# PWR_MGMT.net
KiCad netlist of a schematic drawn in Altium Designer
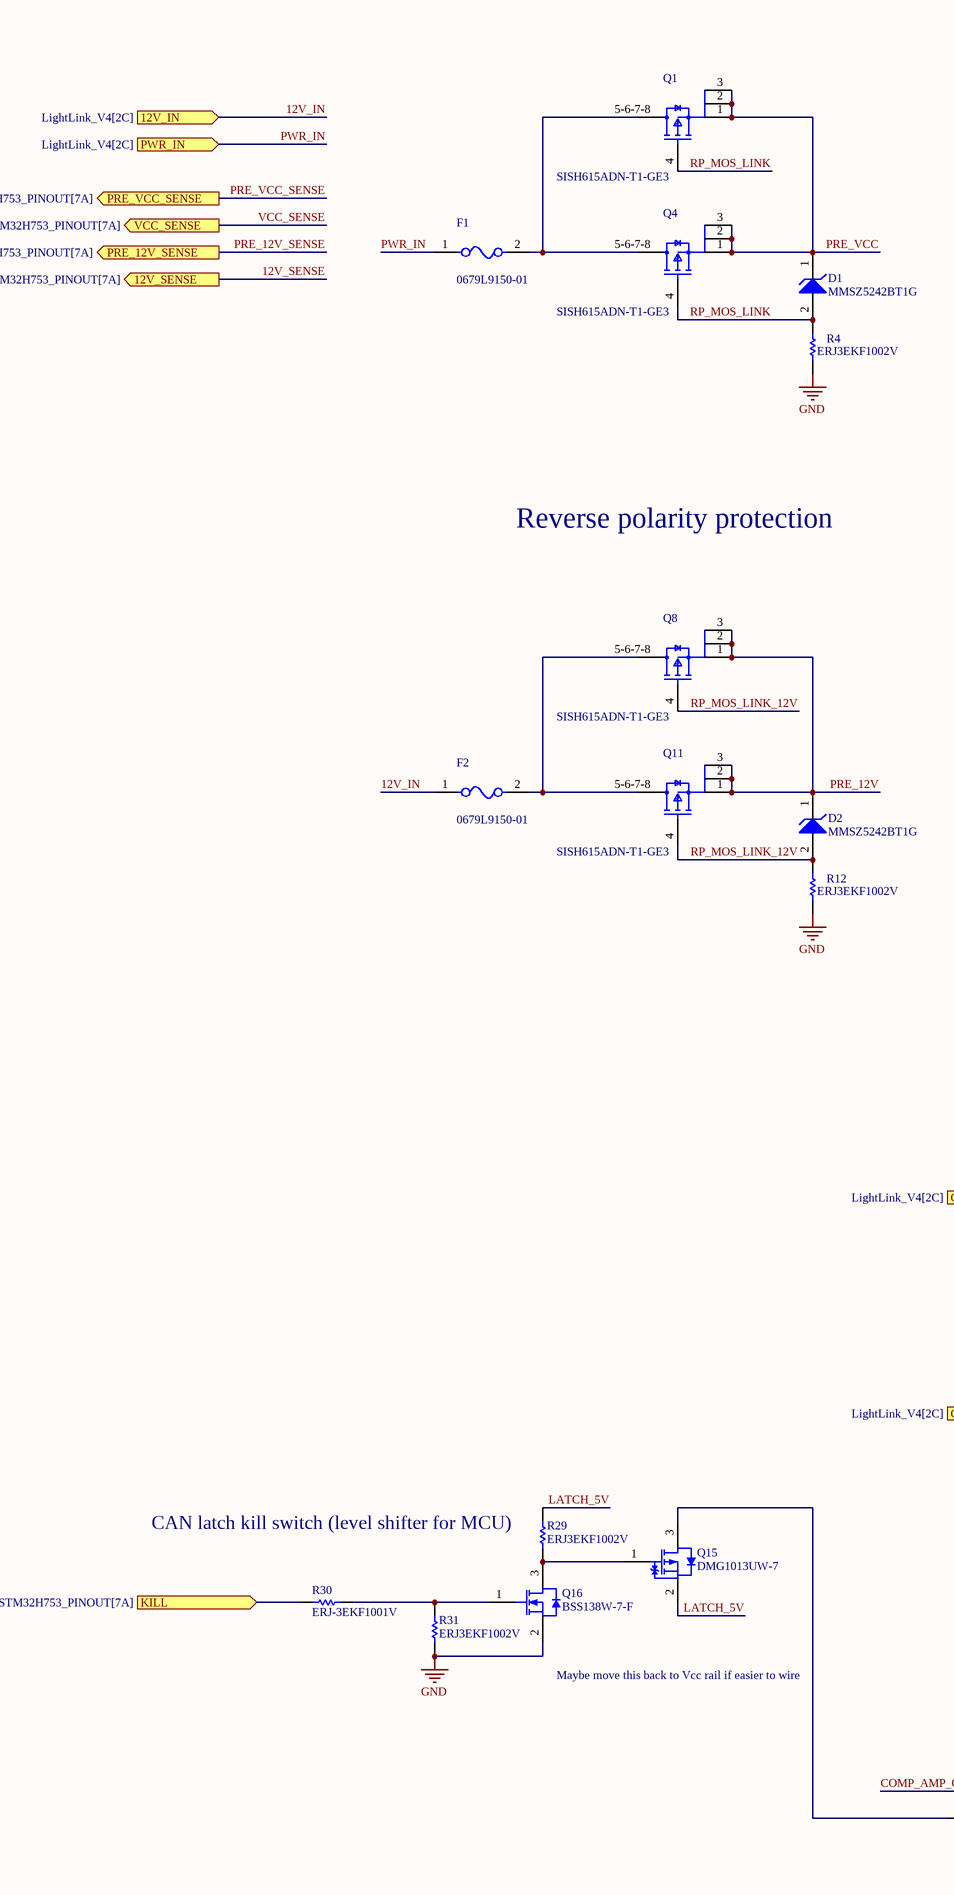
[diagram p0: PWR_MGMT.SchDoc, left]
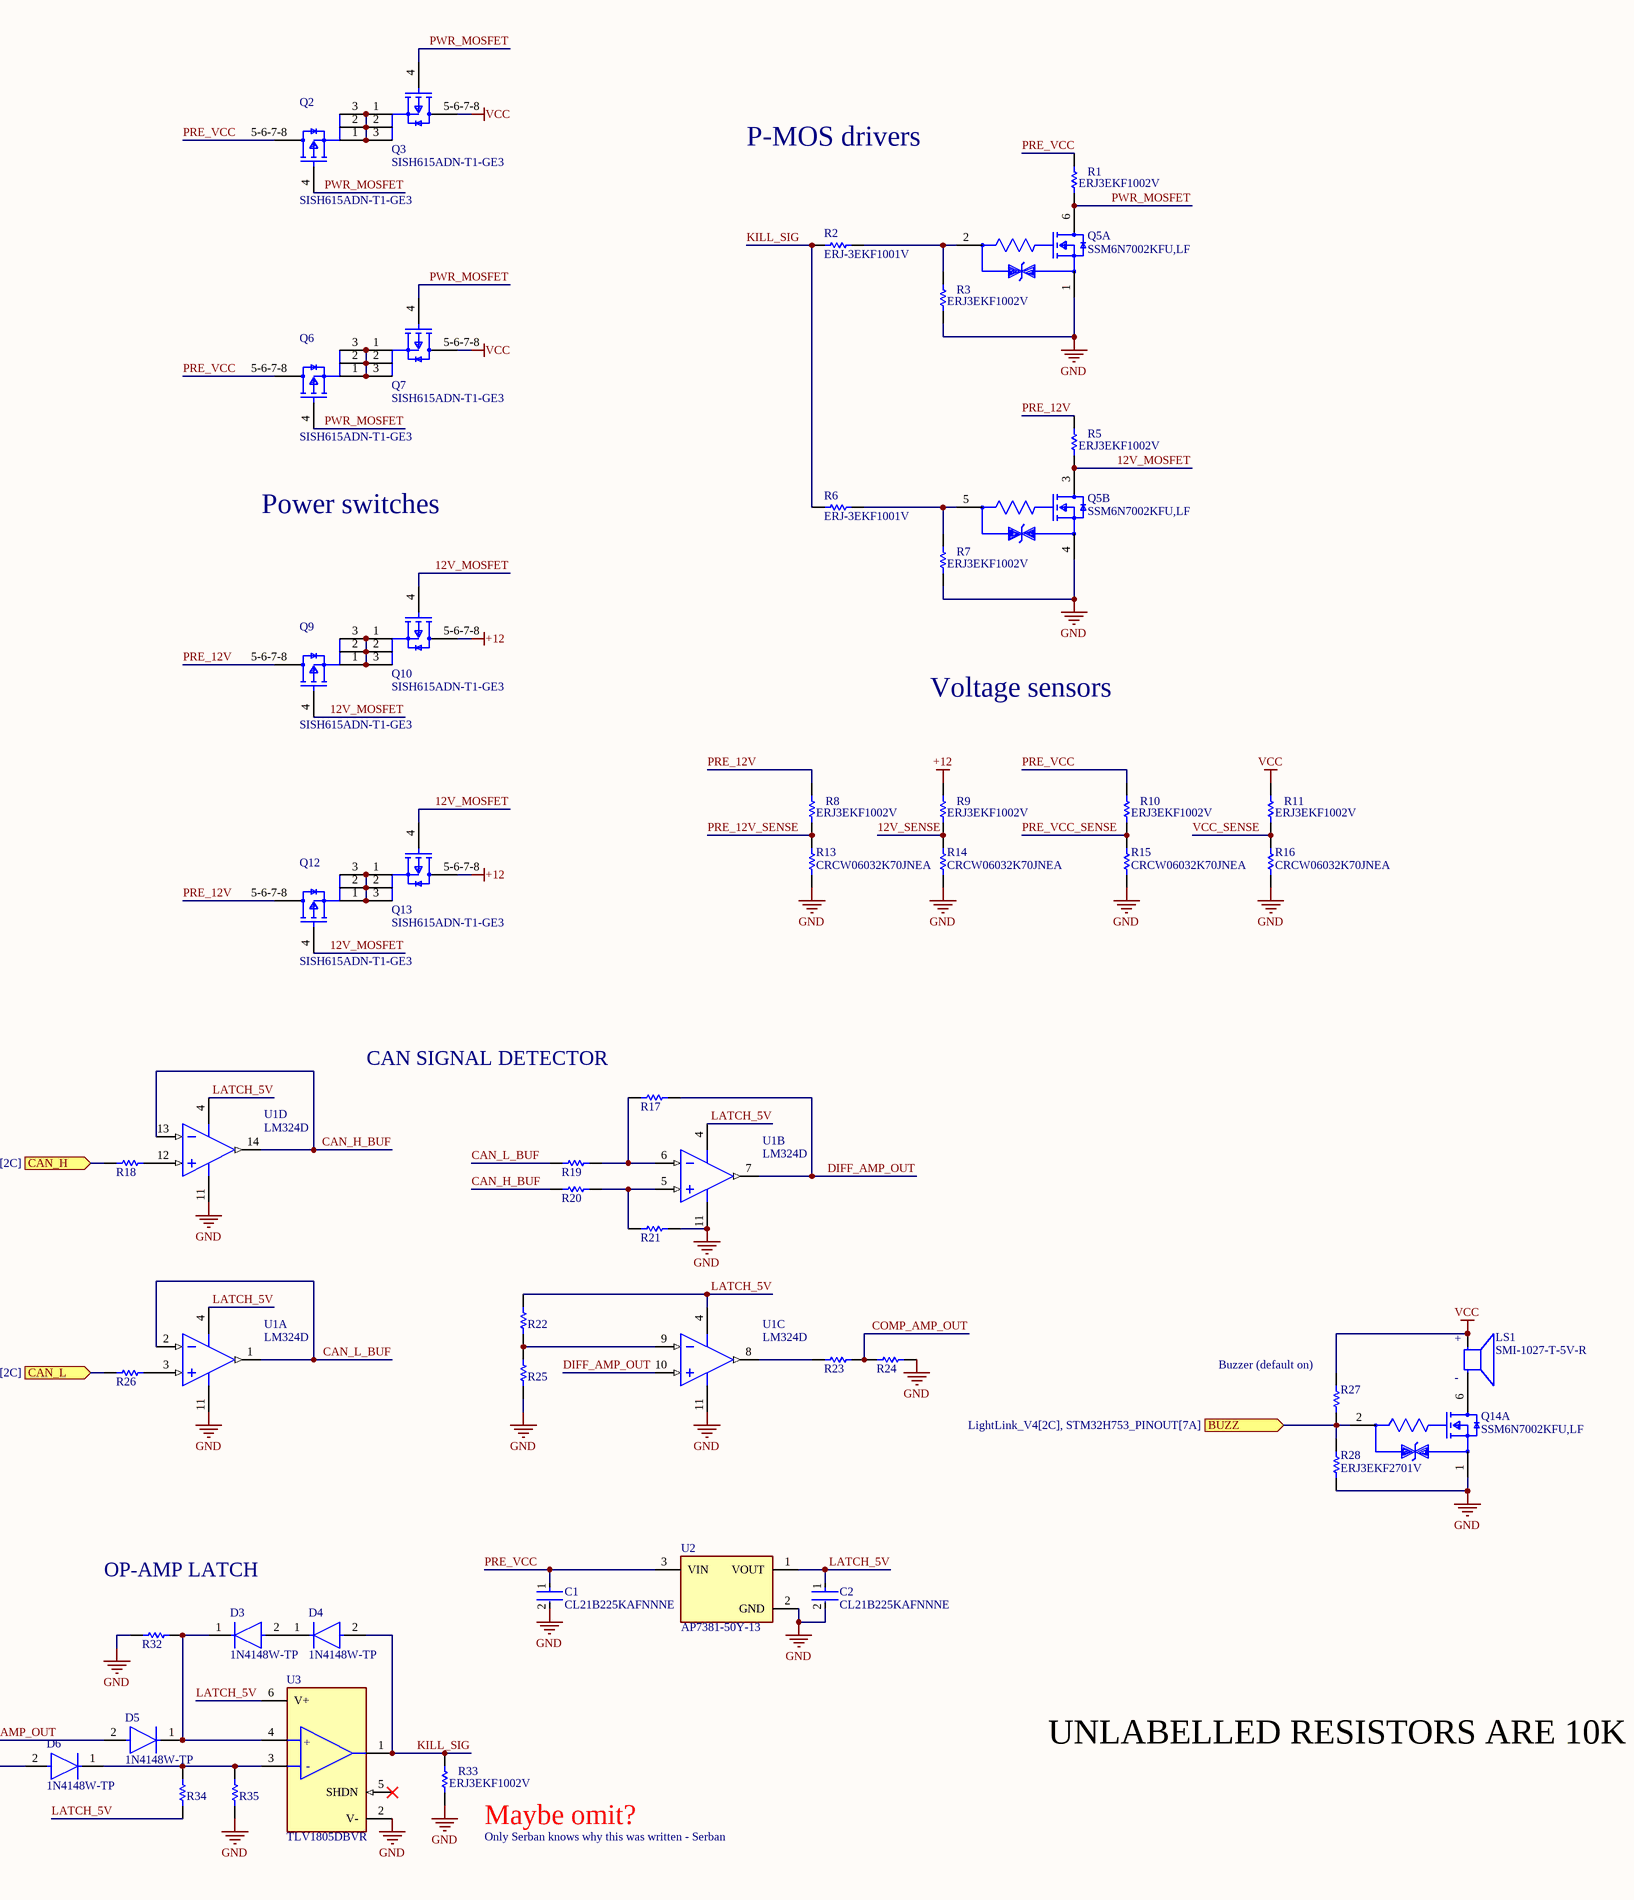
[diagram p1: PWR_MGMT.SchDoc, right]

(export (version "E")
  (design (tool "Eeschema 10.0.6"))
  (components
    (comp (ref "C1")
      (value "CL21B225KAFNNNE")
      (footprint "FP-0805-L_2_01_0_2-W_1_25-IPC_B")
      (fields (field (name "TOLERANCE") "10%") (field (name "VOLTAGE") "25V"))
      (libsource (lib "Altium Content Vault") (part "02cd4be3c70576c341d710602a673aa"))
    )
    (comp (ref "C2")
      (value "CL21B225KAFNNNE")
      (footprint "FP-0805-L_2_01_0_2-W_1_25-IPC_B")
      (fields (field (name "TOLERANCE") "10%") (field (name "VOLTAGE") "25V"))
      (libsource (lib "Altium Content Vault") (part "02cd4be3c70576c341d710602a673aa"))
    )
    (comp (ref "D1")
      (value "MMSZ5242BT1G")
      (footprint "ONSC-SOD-123-2-425-04_V")
      (description "Zener Voltage Regulator, 500 mW, 2-Pin SOD-123, Pb-Free, Tape and Reel")
      (fields (field (name "MANUFACTURER") "On Semiconductor"))
      (libsource (lib "Altium Content Vault") (part "ONSC-K1A2-2"))
    )
    (comp (ref "D2")
      (value "MMSZ5242BT1G")
      (footprint "ONSC-SOD-123-2-425-04_V")
      (description "Zener Voltage Regulator, 500 mW, 2-Pin SOD-123, Pb-Free, Tape and Reel")
      (fields (field (name "MANUFACTURER") "On Semiconductor"))
      (libsource (lib "Altium Content Vault") (part "ONSC-K1A2-2"))
    )
    (comp (ref "D3")
      (value "1N4148W-TP")
      (footprint "FP-SOD-123-IPC_A")
      (description "DIODE GEN PURP 100V 150MA SOD123")
      (libsource (lib "Altium Content Vault") (part "d7152d700b627762746794eb795d46e"))
    )
    (comp (ref "D4")
      (value "1N4148W-TP")
      (footprint "FP-SOD-123-IPC_A")
      (description "DIODE GEN PURP 100V 150MA SOD123")
      (libsource (lib "Altium Content Vault") (part "d7152d700b627762746794eb795d46e"))
    )
    (comp (ref "D5")
      (value "1N4148W-TP")
      (footprint "FP-SOD-123-IPC_A")
      (description "DIODE GEN PURP 100V 150MA SOD123")
      (libsource (lib "Altium Content Vault") (part "d7152d700b627762746794eb795d46e"))
    )
    (comp (ref "D6")
      (value "1N4148W-TP")
      (footprint "FP-SOD-123-IPC_A")
      (description "DIODE GEN PURP 100V 150MA SOD123")
      (libsource (lib "Altium Content Vault") (part "d7152d700b627762746794eb795d46e"))
    )
    (comp (ref "F1")
      (value "0679L9150-01")
      (footprint "FP-0679L-MFG")
      (description "FUSE BRD MNT 15A 125VAC/VDC")
      (fields
        (field (name "OCTOPART") "https://octopart.com/0679l9150-01-bel+fuse-70850665")
        (field (name "MANUFACTURER") "Bel Fuse")
      )
      (libsource (lib "Altium Content Vault") (part "5bcf9b9f640e542cf0359d10258e979"))
    )
    (comp (ref "F2")
      (value "0679L9150-01")
      (footprint "FP-0679L-MFG")
      (description "FUSE BRD MNT 15A 125VAC/VDC")
      (fields
        (field (name "OCTOPART") "https://octopart.com/0679l9150-01-bel+fuse-70850665")
        (field (name "MANUFACTURER") "Bel Fuse")
      )
      (libsource (lib "Altium Content Vault") (part "5bcf9b9f640e542cf0359d10258e979"))
    )
    (comp (ref "LS1")
      (value "SMI-1027-T-5V-R")
      (footprint "SMI-1027-T-5V-R-Footprint-1")
      (description "Audio Ind Magnt 5V 9.6X9.6MM SMD")
      (libsource (lib "uORocketry Hardware") (part "SMI-1027-T-5V-R"))
    )
    (comp (ref "Q1")
      (value "SISH615ADN-T1-GE3")
      (footprint "SISH615ADN-T1-GE3-Footprint-1")
      (description "Trans MOSFET P-CH 20V 22.1A 8-Pin PowerPAK 1212 EP T/R")
      (libsource (lib "uORocketry Hardware") (part "SISH615ADN-T1-GE3-Symbol-1"))
    )
    (comp (ref "Q2")
      (value "SISH615ADN-T1-GE3")
      (footprint "SISH615ADN-T1-GE3-Footprint-1")
      (description "Trans MOSFET P-CH 20V 22.1A 8-Pin PowerPAK 1212 EP T/R")
      (libsource (lib "uORocketry Hardware") (part "SISH615ADN-T1-GE3-Symbol-1"))
    )
    (comp (ref "Q3")
      (value "SISH615ADN-T1-GE3")
      (footprint "SISH615ADN-T1-GE3-Footprint-1")
      (description "Trans MOSFET P-CH 20V 22.1A 8-Pin PowerPAK 1212 EP T/R")
      (libsource (lib "uORocketry Hardware") (part "SISH615ADN-T1-GE3-Symbol-1"))
    )
    (comp (ref "Q4")
      (value "SISH615ADN-T1-GE3")
      (footprint "SISH615ADN-T1-GE3-Footprint-1")
      (description "Trans MOSFET P-CH 20V 22.1A 8-Pin PowerPAK 1212 EP T/R")
      (libsource (lib "uORocketry Hardware") (part "SISH615ADN-T1-GE3-Symbol-1"))
    )
    (comp (ref "Q5")
      (value "SSM6N7002KFU,LF")
      (footprint "FP-SSOP6-P-0_65A-MFG")
      (description "MOSFET 2N-CH 60V 0.3A")
      (libsource (lib "Altium Content Vault") (part "088aa6ac103fdeebe0d1c52ece6b7b9"))
    )
    (comp (ref "Q6")
      (value "SISH615ADN-T1-GE3")
      (footprint "SISH615ADN-T1-GE3-Footprint-1")
      (description "Trans MOSFET P-CH 20V 22.1A 8-Pin PowerPAK 1212 EP T/R")
      (libsource (lib "uORocketry Hardware") (part "SISH615ADN-T1-GE3-Symbol-1"))
    )
    (comp (ref "Q7")
      (value "SISH615ADN-T1-GE3")
      (footprint "SISH615ADN-T1-GE3-Footprint-1")
      (description "Trans MOSFET P-CH 20V 22.1A 8-Pin PowerPAK 1212 EP T/R")
      (libsource (lib "uORocketry Hardware") (part "SISH615ADN-T1-GE3-Symbol-1"))
    )
    (comp (ref "Q8")
      (value "SISH615ADN-T1-GE3")
      (footprint "SISH615ADN-T1-GE3-Footprint-1")
      (description "Trans MOSFET P-CH 20V 22.1A 8-Pin PowerPAK 1212 EP T/R")
      (libsource (lib "uORocketry Hardware") (part "SISH615ADN-T1-GE3-Symbol-1"))
    )
    (comp (ref "Q9")
      (value "SISH615ADN-T1-GE3")
      (footprint "SISH615ADN-T1-GE3-Footprint-1")
      (description "Trans MOSFET P-CH 20V 22.1A 8-Pin PowerPAK 1212 EP T/R")
      (libsource (lib "uORocketry Hardware") (part "SISH615ADN-T1-GE3-Symbol-1"))
    )
    (comp (ref "Q10")
      (value "SISH615ADN-T1-GE3")
      (footprint "SISH615ADN-T1-GE3-Footprint-1")
      (description "Trans MOSFET P-CH 20V 22.1A 8-Pin PowerPAK 1212 EP T/R")
      (libsource (lib "uORocketry Hardware") (part "SISH615ADN-T1-GE3-Symbol-1"))
    )
    (comp (ref "Q11")
      (value "SISH615ADN-T1-GE3")
      (footprint "SISH615ADN-T1-GE3-Footprint-1")
      (description "Trans MOSFET P-CH 20V 22.1A 8-Pin PowerPAK 1212 EP T/R")
      (libsource (lib "uORocketry Hardware") (part "SISH615ADN-T1-GE3-Symbol-1"))
    )
    (comp (ref "Q12")
      (value "SISH615ADN-T1-GE3")
      (footprint "SISH615ADN-T1-GE3-Footprint-1")
      (description "Trans MOSFET P-CH 20V 22.1A 8-Pin PowerPAK 1212 EP T/R")
      (libsource (lib "uORocketry Hardware") (part "SISH615ADN-T1-GE3-Symbol-1"))
    )
    (comp (ref "Q13")
      (value "SISH615ADN-T1-GE3")
      (footprint "SISH615ADN-T1-GE3-Footprint-1")
      (description "Trans MOSFET P-CH 20V 22.1A 8-Pin PowerPAK 1212 EP T/R")
      (libsource (lib "uORocketry Hardware") (part "SISH615ADN-T1-GE3-Symbol-1"))
    )
    (comp (ref "Q14")
      (value "SSM6N7002KFU,LF")
      (footprint "FP-SSOP6-P-0_65A-MFG")
      (description "MOSFET 2N-CH 60V 0.3A")
      (libsource (lib "Altium Content Vault") (part "088aa6ac103fdeebe0d1c52ece6b7b9"))
    )
    (comp (ref "Q15")
      (value "DMG1013UW-7")
      (footprint "DIOD-SOT323-3_V")
      (fields (field (name "MANUFACTURER") "Diodes Inc"))
      (libsource (lib "Altium Content Vault") (part "PEMOS-GSD-3_C"))
    )
    (comp (ref "Q16")
      (value "BSS138W-7-F")
      (footprint "DIOD-SOT323-3_V")
      (fields (field (name "MANUFACTURER") "DiodesIncorporated"))
      (libsource (lib "Altium Content Vault") (part "NEMOS-GSD-3"))
    )
    (comp (ref "R1")
      (value "ERJ3EKF1002V")
      (footprint "RESC1609X55X30LL15T15")
      (description "Chip Resistor, 10 KOhm, +/- 1%, 0.1 W, -55 to 155 degC, 0603 (1608 Metric), RoHS, Tape and Reel")
      (fields (field (name "TOLERANCE") "1%") (field (name "MANUFACTURER") "Panasonic"))
      (libsource (lib "Altium Content Vault") (part "RES-2"))
    )
    (comp (ref "R2")
      (value "ERJ-3EKF1001V")
      (footprint "RESC1608X55X30LL15T15")
      (fields (field (name "MANUFACTURER") "Panasonic"))
      (libsource (lib "Altium Content Vault") (part "RES"))
    )
    (comp (ref "R3")
      (value "ERJ3EKF1002V")
      (footprint "RESC1609X55X30LL15T15")
      (description "Chip Resistor, 10 KOhm, +/- 1%, 0.1 W, -55 to 155 degC, 0603 (1608 Metric), RoHS, Tape and Reel")
      (fields (field (name "TOLERANCE") "1%") (field (name "MANUFACTURER") "Panasonic"))
      (libsource (lib "Altium Content Vault") (part "RES-2"))
    )
    (comp (ref "R4")
      (value "ERJ3EKF1002V")
      (footprint "RESC1609X55X30LL15T15")
      (description "Chip Resistor, 10 KOhm, +/- 1%, 0.1 W, -55 to 155 degC, 0603 (1608 Metric), RoHS, Tape and Reel")
      (fields (field (name "TOLERANCE") "1%") (field (name "MANUFACTURER") "Panasonic"))
      (libsource (lib "Altium Content Vault") (part "RES-2"))
    )
    (comp (ref "R5")
      (value "ERJ3EKF1002V")
      (footprint "RESC1609X55X30LL15T15")
      (description "Chip Resistor, 10 KOhm, +/- 1%, 0.1 W, -55 to 155 degC, 0603 (1608 Metric), RoHS, Tape and Reel")
      (fields (field (name "TOLERANCE") "1%") (field (name "MANUFACTURER") "Panasonic"))
      (libsource (lib "Altium Content Vault") (part "RES-2"))
    )
    (comp (ref "R6")
      (value "ERJ-3EKF1001V")
      (footprint "RESC1608X55X30LL15T15")
      (fields (field (name "MANUFACTURER") "Panasonic"))
      (libsource (lib "Altium Content Vault") (part "RES"))
    )
    (comp (ref "R7")
      (value "ERJ3EKF1002V")
      (footprint "RESC1609X55X30LL15T15")
      (description "Chip Resistor, 10 KOhm, +/- 1%, 0.1 W, -55 to 155 degC, 0603 (1608 Metric), RoHS, Tape and Reel")
      (fields (field (name "TOLERANCE") "1%") (field (name "MANUFACTURER") "Panasonic"))
      (libsource (lib "Altium Content Vault") (part "RES-2"))
    )
    (comp (ref "R8")
      (value "ERJ3EKF1002V")
      (footprint "RESC1609X55X30LL15T15")
      (description "Chip Resistor, 10 KOhm, +/- 1%, 0.1 W, -55 to 155 degC, 0603 (1608 Metric), RoHS, Tape and Reel")
      (fields (field (name "TOLERANCE") "1%") (field (name "MANUFACTURER") "Panasonic"))
      (libsource (lib "Altium Content Vault") (part "RES-2"))
    )
    (comp (ref "R9")
      (value "ERJ3EKF1002V")
      (footprint "RESC1609X55X30LL15T15")
      (description "Chip Resistor, 10 KOhm, +/- 1%, 0.1 W, -55 to 155 degC, 0603 (1608 Metric), RoHS, Tape and Reel")
      (fields (field (name "TOLERANCE") "1%") (field (name "MANUFACTURER") "Panasonic"))
      (libsource (lib "Altium Content Vault") (part "RES-2"))
    )
    (comp (ref "R10")
      (value "ERJ3EKF1002V")
      (footprint "RESC1609X55X30LL15T15")
      (description "Chip Resistor, 10 KOhm, +/- 1%, 0.1 W, -55 to 155 degC, 0603 (1608 Metric), RoHS, Tape and Reel")
      (fields (field (name "TOLERANCE") "1%") (field (name "MANUFACTURER") "Panasonic"))
      (libsource (lib "Altium Content Vault") (part "RES-2"))
    )
    (comp (ref "R11")
      (value "ERJ3EKF1002V")
      (footprint "RESC1609X55X30LL15T15")
      (description "Chip Resistor, 10 KOhm, +/- 1%, 0.1 W, -55 to 155 degC, 0603 (1608 Metric), RoHS, Tape and Reel")
      (fields (field (name "TOLERANCE") "1%") (field (name "MANUFACTURER") "Panasonic"))
      (libsource (lib "Altium Content Vault") (part "RES-2"))
    )
    (comp (ref "R12")
      (value "ERJ3EKF1002V")
      (footprint "RESC1609X55X30LL15T15")
      (description "Chip Resistor, 10 KOhm, +/- 1%, 0.1 W, -55 to 155 degC, 0603 (1608 Metric), RoHS, Tape and Reel")
      (fields (field (name "TOLERANCE") "1%") (field (name "MANUFACTURER") "Panasonic"))
      (libsource (lib "Altium Content Vault") (part "RES-2"))
    )
    (comp (ref "R13")
      (value "CRCW06032K70JNEA")
      (footprint "RESC1609X50X30ML10T20")
      (fields (field (name "MANUFACTURER") "Vishay Dale"))
      (libsource (lib "Altium Content Vault") (part "RES"))
    )
    (comp (ref "R14")
      (value "CRCW06032K70JNEA")
      (footprint "RESC1609X50X30ML10T20")
      (fields (field (name "MANUFACTURER") "Vishay Dale"))
      (libsource (lib "Altium Content Vault") (part "RES"))
    )
    (comp (ref "R15")
      (value "CRCW06032K70JNEA")
      (footprint "RESC1609X50X30ML10T20")
      (fields (field (name "MANUFACTURER") "Vishay Dale"))
      (libsource (lib "Altium Content Vault") (part "RES"))
    )
    (comp (ref "R16")
      (value "CRCW06032K70JNEA")
      (footprint "RESC1609X50X30ML10T20")
      (fields (field (name "MANUFACTURER") "Vishay Dale"))
      (libsource (lib "Altium Content Vault") (part "RES"))
    )
    (comp (ref "R17")
      (value "ERJ3EKF1002V")
      (footprint "RESC1609X55X30LL15T15")
      (description "Chip Resistor, 10 KOhm, +/- 1%, 0.1 W, -55 to 155 degC, 0603 (1608 Metric), RoHS, Tape and Reel")
      (fields (field (name "TOLERANCE") "1%") (field (name "MANUFACTURER") "Panasonic"))
      (libsource (lib "Altium Content Vault") (part "RES-2"))
    )
    (comp (ref "R18")
      (value "ERJ3EKF1002V")
      (footprint "RESC1609X55X30LL15T15")
      (description "Chip Resistor, 10 KOhm, +/- 1%, 0.1 W, -55 to 155 degC, 0603 (1608 Metric), RoHS, Tape and Reel")
      (fields (field (name "TOLERANCE") "1%") (field (name "MANUFACTURER") "Panasonic"))
      (libsource (lib "Altium Content Vault") (part "RES-2"))
    )
    (comp (ref "R19")
      (value "ERJ3EKF1002V")
      (footprint "RESC1609X55X30LL15T15")
      (description "Chip Resistor, 10 KOhm, +/- 1%, 0.1 W, -55 to 155 degC, 0603 (1608 Metric), RoHS, Tape and Reel")
      (fields (field (name "TOLERANCE") "1%") (field (name "MANUFACTURER") "Panasonic"))
      (libsource (lib "Altium Content Vault") (part "RES-2"))
    )
    (comp (ref "R20")
      (value "ERJ3EKF1002V")
      (footprint "RESC1609X55X30LL15T15")
      (description "Chip Resistor, 10 KOhm, +/- 1%, 0.1 W, -55 to 155 degC, 0603 (1608 Metric), RoHS, Tape and Reel")
      (fields (field (name "TOLERANCE") "1%") (field (name "MANUFACTURER") "Panasonic"))
      (libsource (lib "Altium Content Vault") (part "RES-2"))
    )
    (comp (ref "R21")
      (value "ERJ3EKF1002V")
      (footprint "RESC1609X55X30LL15T15")
      (description "Chip Resistor, 10 KOhm, +/- 1%, 0.1 W, -55 to 155 degC, 0603 (1608 Metric), RoHS, Tape and Reel")
      (fields (field (name "TOLERANCE") "1%") (field (name "MANUFACTURER") "Panasonic"))
      (libsource (lib "Altium Content Vault") (part "RES-2"))
    )
    (comp (ref "R22")
      (value "ERJ3EKF1002V")
      (footprint "RESC1609X55X30LL15T15")
      (description "Chip Resistor, 10 KOhm, +/- 1%, 0.1 W, -55 to 155 degC, 0603 (1608 Metric), RoHS, Tape and Reel")
      (fields (field (name "TOLERANCE") "1%") (field (name "MANUFACTURER") "Panasonic"))
      (libsource (lib "Altium Content Vault") (part "RES-2"))
    )
    (comp (ref "R23")
      (value "ERJ3EKF1002V")
      (footprint "RESC1609X55X30LL15T15")
      (description "Chip Resistor, 10 KOhm, +/- 1%, 0.1 W, -55 to 155 degC, 0603 (1608 Metric), RoHS, Tape and Reel")
      (fields (field (name "TOLERANCE") "1%") (field (name "MANUFACTURER") "Panasonic"))
      (libsource (lib "Altium Content Vault") (part "RES-2"))
    )
    (comp (ref "R24")
      (value "ERJ3EKF1002V")
      (footprint "RESC1609X55X30LL15T15")
      (description "Chip Resistor, 10 KOhm, +/- 1%, 0.1 W, -55 to 155 degC, 0603 (1608 Metric), RoHS, Tape and Reel")
      (fields (field (name "TOLERANCE") "1%") (field (name "MANUFACTURER") "Panasonic"))
      (libsource (lib "Altium Content Vault") (part "RES-2"))
    )
    (comp (ref "R25")
      (value "ERJ-3EKF1001V")
      (footprint "RESC1608X55X30LL15T15")
      (fields (field (name "MANUFACTURER") "Panasonic"))
      (libsource (lib "Altium Content Vault") (part "RES"))
    )
    (comp (ref "R26")
      (value "ERJ3EKF1002V")
      (footprint "RESC1609X55X30LL15T15")
      (description "Chip Resistor, 10 KOhm, +/- 1%, 0.1 W, -55 to 155 degC, 0603 (1608 Metric), RoHS, Tape and Reel")
      (fields (field (name "TOLERANCE") "1%") (field (name "MANUFACTURER") "Panasonic"))
      (libsource (lib "Altium Content Vault") (part "RES-2"))
    )
    (comp (ref "R27")
      (value "ERJ3EKF1002V")
      (footprint "RESC1609X55X30LL15T15")
      (description "Chip Resistor, 10 KOhm, +/- 1%, 0.1 W, -55 to 155 degC, 0603 (1608 Metric), RoHS, Tape and Reel")
      (fields (field (name "TOLERANCE") "1%") (field (name "MANUFACTURER") "Panasonic"))
      (libsource (lib "Altium Content Vault") (part "RES-2"))
    )
    (comp (ref "R28")
      (value "ERJ3EKF2701V")
      (footprint "RESC1608X55X30LL15T15")
      (fields (field (name "MANUFACTURER") "Panasonic"))
      (libsource (lib "Altium Content Vault") (part "RES"))
    )
    (comp (ref "R29")
      (value "ERJ3EKF1002V")
      (footprint "RESC1609X55X30LL15T15")
      (description "Chip Resistor, 10 KOhm, +/- 1%, 0.1 W, -55 to 155 degC, 0603 (1608 Metric), RoHS, Tape and Reel")
      (fields (field (name "TOLERANCE") "1%") (field (name "MANUFACTURER") "Panasonic"))
      (libsource (lib "Altium Content Vault") (part "RES-2"))
    )
    (comp (ref "R30")
      (value "ERJ-3EKF1001V")
      (footprint "RESC1608X55X30LL15T15")
      (fields (field (name "MANUFACTURER") "Panasonic"))
      (libsource (lib "Altium Content Vault") (part "RES"))
    )
    (comp (ref "R31")
      (value "ERJ3EKF1002V")
      (footprint "RESC1609X55X30LL15T15")
      (description "Chip Resistor, 10 KOhm, +/- 1%, 0.1 W, -55 to 155 degC, 0603 (1608 Metric), RoHS, Tape and Reel")
      (fields (field (name "TOLERANCE") "1%") (field (name "MANUFACTURER") "Panasonic"))
      (libsource (lib "Altium Content Vault") (part "RES-2"))
    )
    (comp (ref "R32")
      (value "ERJ3EKF1002V")
      (footprint "RESC1609X55X30LL15T15")
      (description "Chip Resistor, 10 KOhm, +/- 1%, 0.1 W, -55 to 155 degC, 0603 (1608 Metric), RoHS, Tape and Reel")
      (fields (field (name "TOLERANCE") "1%") (field (name "MANUFACTURER") "Panasonic"))
      (libsource (lib "Altium Content Vault") (part "RES-2"))
    )
    (comp (ref "R33")
      (value "ERJ3EKF1002V")
      (footprint "RESC1609X55X30LL15T15")
      (description "Chip Resistor, 10 KOhm, +/- 1%, 0.1 W, -55 to 155 degC, 0603 (1608 Metric), RoHS, Tape and Reel")
      (fields (field (name "TOLERANCE") "1%") (field (name "MANUFACTURER") "Panasonic"))
      (libsource (lib "Altium Content Vault") (part "RES-2"))
    )
    (comp (ref "R34")
      (value "ERJ3EKF1002V")
      (footprint "RESC1609X55X30LL15T15")
      (description "Chip Resistor, 10 KOhm, +/- 1%, 0.1 W, -55 to 155 degC, 0603 (1608 Metric), RoHS, Tape and Reel")
      (fields (field (name "TOLERANCE") "1%") (field (name "MANUFACTURER") "Panasonic"))
      (libsource (lib "Altium Content Vault") (part "RES-2"))
    )
    (comp (ref "R35")
      (value "ERJ3EKF1002V")
      (footprint "RESC1609X55X30LL15T15")
      (description "Chip Resistor, 10 KOhm, +/- 1%, 0.1 W, -55 to 155 degC, 0603 (1608 Metric), RoHS, Tape and Reel")
      (fields (field (name "TOLERANCE") "1%") (field (name "MANUFACTURER") "Panasonic"))
      (libsource (lib "Altium Content Vault") (part "RES-2"))
    )
    (comp (ref "U1")
      (value "LM324D")
      (footprint "D0014A_L")
      (fields (field (name "MANUFACTURER") "Texas Instruments"))
      (libsource (lib "Altium Content Vault") (part "TI-LMX24_2902X-X14"))
    )
    (comp (ref "U2")
      (value "AP7381-50Y-13")
      (footprint "FP-SOT89-MFG")
      (description "IC REG LINEAR 5V 150MA SOT89")
      (fields
        (field (name "MANUFACTURER") "Diodes Inc.")
        (field (name "OCTOPART") "https://octopart.com/ap7381-50y-13-diodes+inc.-87775116")
      )
      (libsource (lib "Altium Content Vault") (part "4c3da590f2d7b1882ad42f13e6d336b"))
    )
    (comp (ref "U3")
      (value "TLV1805DBVR")
      (footprint "FP-DBV0006A-IPC_C")
      (description "40V, RAIL-TO-RAIL INPUT, PUSH-PU")
      (libsource (lib "Altium Content Vault") (part "c7aa3bc3dbf0dc8b0b0354779bd1228"))
    )
  )
  (nets
    (net (code "1") (name "+12") (class "Default")
      (node (ref "Q10") (pin "5-6-7-8") (pinfunction "D_5-6-7-8") (pintype "passive"))
      (node (ref "Q13") (pin "5-6-7-8") (pinfunction "D_5-6-7-8") (pintype "passive"))
      (node (ref "R9") (pin "1") (pinfunction "1_1") (pintype "passive"))
    )
    (net (code "2") (name "/12V_IN") (class "Default")
      (node (ref "F2") (pin "1") (pinfunction "1_1") (pintype "passive"))
    )
    (net (code "3") (name "/12V_MOSFET") (class "Default")
      (node (ref "Q10") (pin "4") (pinfunction "G_4") (pintype "passive"))
      (node (ref "Q12") (pin "4") (pinfunction "G_4") (pintype "passive"))
      (node (ref "Q13") (pin "4") (pinfunction "G_4") (pintype "passive"))
      (node (ref "Q5") (pin "3") (pinfunction "Drain2_3") (pintype "passive"))
      (node (ref "Q9") (pin "4") (pinfunction "G_4") (pintype "passive"))
      (node (ref "R5") (pin "2") (pinfunction "2_2") (pintype "passive"))
    )
    (net (code "4") (name "/12V_SENSE") (class "Default")
      (node (ref "R14") (pin "2") (pinfunction "2_2") (pintype "passive"))
      (node (ref "R9") (pin "2") (pinfunction "2_2") (pintype "passive"))
    )
    (net (code "5") (name "/BUZZ") (class "Default")
      (node (ref "Q14") (pin "2") (pinfunction "Gate1_2") (pintype "passive"))
      (node (ref "R27") (pin "1") (pinfunction "1_1") (pintype "passive"))
      (node (ref "R28") (pin "2") (pinfunction "2_2") (pintype "passive"))
    )
    (net (code "6") (name "/CAN_H") (class "Default")
      (node (ref "R18") (pin "1") (pinfunction "1_1") (pintype "passive"))
    )
    (net (code "7") (name "/CAN_H_BUF") (class "Default")
      (node (ref "R20") (pin "1") (pinfunction "1_1") (pintype "passive"))
      (node (ref "U1") (pin "13") (pinfunction "4IN-_13") (pintype "input"))
      (node (ref "U1") (pin "14") (pinfunction "4OUT_14") (pintype "output"))
    )
    (net (code "8") (name "/CAN_L") (class "Default")
      (node (ref "R26") (pin "1") (pinfunction "1_1") (pintype "passive"))
    )
    (net (code "9") (name "/CAN_L_BUF") (class "Default")
      (node (ref "R19") (pin "1") (pinfunction "1_1") (pintype "passive"))
      (node (ref "U1") (pin "1") (pinfunction "1OUT_1") (pintype "output"))
      (node (ref "U1") (pin "2") (pinfunction "1IN-_2") (pintype "input"))
    )
    (net (code "10") (name "/COMP_AMP_OUT") (class "Default")
      (node (ref "D5") (pin "2") (pinfunction "A_2") (pintype "passive"))
      (node (ref "R23") (pin "1") (pinfunction "1_1") (pintype "passive"))
      (node (ref "R24") (pin "2") (pinfunction "2_2") (pintype "passive"))
    )
    (net (code "11") (name "/DIFF_AMP_OUT") (class "Default")
      (node (ref "R17") (pin "2") (pinfunction "2_2") (pintype "passive"))
      (node (ref "U1") (pin "10") (pinfunction "3IN+_10") (pintype "input"))
      (node (ref "U1") (pin "7") (pinfunction "2OUT_7") (pintype "output"))
    )
    (net (code "12") (name "/KILL") (class "Default")
      (node (ref "R30") (pin "2") (pinfunction "2_2") (pintype "passive"))
    )
    (net (code "13") (name "/KILL_SIG") (class "Default")
      (node (ref "D4") (pin "2") (pinfunction "A_2") (pintype "passive"))
      (node (ref "R2") (pin "1") (pinfunction "1_1") (pintype "passive"))
      (node (ref "R33") (pin "1") (pinfunction "1_1") (pintype "passive"))
      (node (ref "R6") (pin "1") (pinfunction "1_1") (pintype "passive"))
      (node (ref "U3") (pin "1") (pinfunction "OUT_1") (pintype "passive"))
    )
    (net (code "14") (name "/LATCH_5V") (class "Default")
      (node (ref "C2") (pin "1") (pinfunction "1_1") (pintype "passive"))
      (node (ref "Q15") (pin "2") (pinfunction "S_2") (pintype "passive"))
      (node (ref "R22") (pin "2") (pinfunction "2_2") (pintype "passive"))
      (node (ref "R29") (pin "2") (pinfunction "2_2") (pintype "passive"))
      (node (ref "R34") (pin "1") (pinfunction "1_1") (pintype "passive"))
      (node (ref "U1") (pin "4") (pinfunction "VCC_4") (pintype "power_in"))
      (node (ref "U2") (pin "1") (pinfunction "VOUT_1") (pintype "power_in"))
      (node (ref "U3") (pin "6") (pinfunction "V+_6") (pintype "power_in"))
    )
    (net (code "15") (name "/PRE_12V") (class "Default")
      (node (ref "D2") (pin "1") (pinfunction "K_1") (pintype "passive"))
      (node (ref "Q11") (pin "1") (pinfunction "S_1") (pintype "passive"))
      (node (ref "Q11") (pin "2") (pinfunction "S_2") (pintype "passive"))
      (node (ref "Q11") (pin "3") (pinfunction "S_3") (pintype "passive"))
      (node (ref "Q12") (pin "5-6-7-8") (pinfunction "D_5-6-7-8") (pintype "passive"))
      (node (ref "Q8") (pin "1") (pinfunction "S_1") (pintype "passive"))
      (node (ref "Q8") (pin "2") (pinfunction "S_2") (pintype "passive"))
      (node (ref "Q8") (pin "3") (pinfunction "S_3") (pintype "passive"))
      (node (ref "Q9") (pin "5-6-7-8") (pinfunction "D_5-6-7-8") (pintype "passive"))
      (node (ref "R5") (pin "1") (pinfunction "1_1") (pintype "passive"))
      (node (ref "R8") (pin "1") (pinfunction "1_1") (pintype "passive"))
    )
    (net (code "16") (name "/PRE_12V_SENSE") (class "Default")
      (node (ref "R13") (pin "2") (pinfunction "2_2") (pintype "passive"))
      (node (ref "R8") (pin "2") (pinfunction "2_2") (pintype "passive"))
    )
    (net (code "17") (name "/PRE_VCC") (class "Default")
      (node (ref "C1") (pin "1") (pinfunction "1_1") (pintype "passive"))
      (node (ref "D1") (pin "1") (pinfunction "K_1") (pintype "passive"))
      (node (ref "Q1") (pin "1") (pinfunction "S_1") (pintype "passive"))
      (node (ref "Q1") (pin "2") (pinfunction "S_2") (pintype "passive"))
      (node (ref "Q1") (pin "3") (pinfunction "S_3") (pintype "passive"))
      (node (ref "Q2") (pin "5-6-7-8") (pinfunction "D_5-6-7-8") (pintype "passive"))
      (node (ref "Q4") (pin "1") (pinfunction "S_1") (pintype "passive"))
      (node (ref "Q4") (pin "2") (pinfunction "S_2") (pintype "passive"))
      (node (ref "Q4") (pin "3") (pinfunction "S_3") (pintype "passive"))
      (node (ref "Q6") (pin "5-6-7-8") (pinfunction "D_5-6-7-8") (pintype "passive"))
      (node (ref "R1") (pin "1") (pinfunction "1_1") (pintype "passive"))
      (node (ref "R10") (pin "1") (pinfunction "1_1") (pintype "passive"))
      (node (ref "U2") (pin "3") (pinfunction "VIN_3") (pintype "power_in"))
    )
    (net (code "18") (name "/PRE_VCC_SENSE") (class "Default")
      (node (ref "R10") (pin "2") (pinfunction "2_2") (pintype "passive"))
      (node (ref "R15") (pin "2") (pinfunction "2_2") (pintype "passive"))
    )
    (net (code "19") (name "/PWR_IN") (class "Default")
      (node (ref "F1") (pin "1") (pinfunction "1_1") (pintype "passive"))
    )
    (net (code "20") (name "/PWR_MOSFET") (class "Default")
      (node (ref "Q2") (pin "4") (pinfunction "G_4") (pintype "passive"))
      (node (ref "Q3") (pin "4") (pinfunction "G_4") (pintype "passive"))
      (node (ref "Q5") (pin "6") (pinfunction "Drain1_6") (pintype "passive"))
      (node (ref "Q6") (pin "4") (pinfunction "G_4") (pintype "passive"))
      (node (ref "Q7") (pin "4") (pinfunction "G_4") (pintype "passive"))
      (node (ref "R1") (pin "2") (pinfunction "2_2") (pintype "passive"))
    )
    (net (code "21") (name "/RP_MOS_LINK") (class "Default")
      (node (ref "D1") (pin "2") (pinfunction "A_2") (pintype "passive"))
      (node (ref "Q1") (pin "4") (pinfunction "G_4") (pintype "passive"))
      (node (ref "Q4") (pin "4") (pinfunction "G_4") (pintype "passive"))
      (node (ref "R4") (pin "1") (pinfunction "1_1") (pintype "passive"))
    )
    (net (code "22") (name "/RP_MOS_LINK_12V") (class "Default")
      (node (ref "D2") (pin "2") (pinfunction "A_2") (pintype "passive"))
      (node (ref "Q11") (pin "4") (pinfunction "G_4") (pintype "passive"))
      (node (ref "Q8") (pin "4") (pinfunction "G_4") (pintype "passive"))
      (node (ref "R12") (pin "1") (pinfunction "1_1") (pintype "passive"))
    )
    (net (code "23") (name "/VCC_SENSE") (class "Default")
      (node (ref "R11") (pin "2") (pinfunction "2_2") (pintype "passive"))
      (node (ref "R16") (pin "2") (pinfunction "2_2") (pintype "passive"))
    )
    (net (code "24") (name "GND") (class "Default")
      (node (ref "C1") (pin "2") (pinfunction "2_2") (pintype "passive"))
      (node (ref "C2") (pin "2") (pinfunction "2_2") (pintype "passive"))
      (node (ref "Q14") (pin "1") (pinfunction "Source1_1") (pintype "passive"))
      (node (ref "Q16") (pin "2") (pinfunction "S_2") (pintype "passive"))
      (node (ref "Q5") (pin "1") (pinfunction "Source1_1") (pintype "passive"))
      (node (ref "Q5") (pin "4") (pinfunction "Source2_4") (pintype "passive"))
      (node (ref "R12") (pin "2") (pinfunction "2_2") (pintype "passive"))
      (node (ref "R13") (pin "1") (pinfunction "1_1") (pintype "passive"))
      (node (ref "R14") (pin "1") (pinfunction "1_1") (pintype "passive"))
      (node (ref "R15") (pin "1") (pinfunction "1_1") (pintype "passive"))
      (node (ref "R16") (pin "1") (pinfunction "1_1") (pintype "passive"))
      (node (ref "R21") (pin "2") (pinfunction "2_2") (pintype "passive"))
      (node (ref "R24") (pin "1") (pinfunction "1_1") (pintype "passive"))
      (node (ref "R25") (pin "1") (pinfunction "1_1") (pintype "passive"))
      (node (ref "R28") (pin "1") (pinfunction "1_1") (pintype "passive"))
      (node (ref "R3") (pin "2") (pinfunction "2_2") (pintype "passive"))
      (node (ref "R31") (pin "1") (pinfunction "1_1") (pintype "passive"))
      (node (ref "R32") (pin "2") (pinfunction "2_2") (pintype "passive"))
      (node (ref "R33") (pin "2") (pinfunction "2_2") (pintype "passive"))
      (node (ref "R35") (pin "1") (pinfunction "1_1") (pintype "passive"))
      (node (ref "R4") (pin "2") (pinfunction "2_2") (pintype "passive"))
      (node (ref "R7") (pin "2") (pinfunction "2_2") (pintype "passive"))
      (node (ref "U1") (pin "11") (pinfunction "GND_11") (pintype "power_in"))
      (node (ref "U2") (pin "2") (pinfunction "GND_2") (pintype "power_in"))
      (node (ref "U3") (pin "2") (pinfunction "V-_2") (pintype "power_in"))
    )
    (net (code "25") (name "Net-(D3-A)") (class "Default")
      (node (ref "D3") (pin "2") (pinfunction "A_2") (pintype "passive"))
      (node (ref "D4") (pin "1") (pinfunction "C_1") (pintype "passive"))
    )
    (net (code "26") (name "Net-(D3-C)") (class "Default")
      (node (ref "D3") (pin "1") (pinfunction "C_1") (pintype "passive"))
      (node (ref "D5") (pin "1") (pinfunction "C_1") (pintype "passive"))
      (node (ref "R32") (pin "1") (pinfunction "1_1") (pintype "passive"))
      (node (ref "U3") (pin "4") (pinfunction "+IN_4") (pintype "tri_state"))
    )
    (net (code "27") (name "Net-(D6-A)") (class "Default")
      (node (ref "D6") (pin "2") (pinfunction "A_2") (pintype "passive"))
      (node (ref "Q15") (pin "3") (pinfunction "D_3") (pintype "passive"))
    )
    (net (code "28") (name "Net-(D6-C)") (class "Default")
      (node (ref "D6") (pin "1") (pinfunction "C_1") (pintype "passive"))
      (node (ref "R34") (pin "2") (pinfunction "2_2") (pintype "passive"))
      (node (ref "R35") (pin "2") (pinfunction "2_2") (pintype "passive"))
      (node (ref "U3") (pin "3") (pinfunction "-IN_3") (pintype "tri_state"))
    )
    (net (code "29") (name "Net-(LS1-NEG)") (class "Default")
      (node (ref "LS1") (pin "LOAD-") (pinfunction "NEG_LOAD-") (pintype "passive"))
      (node (ref "Q14") (pin "6") (pinfunction "Drain1_6") (pintype "passive"))
    )
    (net (code "30") (name "Net-(Q1-D)") (class "Default")
      (node (ref "F1") (pin "2") (pinfunction "2_2") (pintype "passive"))
      (node (ref "Q1") (pin "5-6-7-8") (pinfunction "D_5-6-7-8") (pintype "passive"))
      (node (ref "Q4") (pin "5-6-7-8") (pinfunction "D_5-6-7-8") (pintype "passive"))
    )
    (net (code "31") (name "Net-(Q2-S-Pad1)") (class "Default")
      (node (ref "Q2") (pin "1") (pinfunction "S_1") (pintype "passive"))
      (node (ref "Q2") (pin "2") (pinfunction "S_2") (pintype "passive"))
      (node (ref "Q2") (pin "3") (pinfunction "S_3") (pintype "passive"))
      (node (ref "Q3") (pin "1") (pinfunction "S_1") (pintype "passive"))
      (node (ref "Q3") (pin "2") (pinfunction "S_2") (pintype "passive"))
      (node (ref "Q3") (pin "3") (pinfunction "S_3") (pintype "passive"))
    )
    (net (code "32") (name "Net-(Q5A-Gate1)") (class "Default")
      (node (ref "Q5") (pin "2") (pinfunction "Gate1_2") (pintype "passive"))
      (node (ref "R2") (pin "2") (pinfunction "2_2") (pintype "passive"))
      (node (ref "R3") (pin "1") (pinfunction "1_1") (pintype "passive"))
    )
    (net (code "33") (name "Net-(Q5B-Gate2)") (class "Default")
      (node (ref "Q5") (pin "5") (pinfunction "Gate2_5") (pintype "passive"))
      (node (ref "R6") (pin "2") (pinfunction "2_2") (pintype "passive"))
      (node (ref "R7") (pin "1") (pinfunction "1_1") (pintype "passive"))
    )
    (net (code "34") (name "Net-(Q6-S-Pad1)") (class "Default")
      (node (ref "Q6") (pin "1") (pinfunction "S_1") (pintype "passive"))
      (node (ref "Q6") (pin "2") (pinfunction "S_2") (pintype "passive"))
      (node (ref "Q6") (pin "3") (pinfunction "S_3") (pintype "passive"))
      (node (ref "Q7") (pin "1") (pinfunction "S_1") (pintype "passive"))
      (node (ref "Q7") (pin "2") (pinfunction "S_2") (pintype "passive"))
      (node (ref "Q7") (pin "3") (pinfunction "S_3") (pintype "passive"))
    )
    (net (code "35") (name "Net-(Q10-S-Pad1)") (class "Default")
      (node (ref "Q10") (pin "1") (pinfunction "S_1") (pintype "passive"))
      (node (ref "Q10") (pin "2") (pinfunction "S_2") (pintype "passive"))
      (node (ref "Q10") (pin "3") (pinfunction "S_3") (pintype "passive"))
      (node (ref "Q9") (pin "1") (pinfunction "S_1") (pintype "passive"))
      (node (ref "Q9") (pin "2") (pinfunction "S_2") (pintype "passive"))
      (node (ref "Q9") (pin "3") (pinfunction "S_3") (pintype "passive"))
    )
    (net (code "36") (name "Net-(Q11-D)") (class "Default")
      (node (ref "F2") (pin "2") (pinfunction "2_2") (pintype "passive"))
      (node (ref "Q11") (pin "5-6-7-8") (pinfunction "D_5-6-7-8") (pintype "passive"))
      (node (ref "Q8") (pin "5-6-7-8") (pinfunction "D_5-6-7-8") (pintype "passive"))
    )
    (net (code "37") (name "Net-(Q12-S-Pad1)") (class "Default")
      (node (ref "Q12") (pin "1") (pinfunction "S_1") (pintype "passive"))
      (node (ref "Q12") (pin "2") (pinfunction "S_2") (pintype "passive"))
      (node (ref "Q12") (pin "3") (pinfunction "S_3") (pintype "passive"))
      (node (ref "Q13") (pin "1") (pinfunction "S_1") (pintype "passive"))
      (node (ref "Q13") (pin "2") (pinfunction "S_2") (pintype "passive"))
      (node (ref "Q13") (pin "3") (pinfunction "S_3") (pintype "passive"))
    )
    (net (code "38") (name "Net-(Q15-G)") (class "Default")
      (node (ref "Q15") (pin "1") (pinfunction "G_1") (pintype "passive"))
      (node (ref "Q16") (pin "3") (pinfunction "D_3") (pintype "passive"))
      (node (ref "R29") (pin "1") (pinfunction "1_1") (pintype "passive"))
    )
    (net (code "39") (name "Net-(Q16-G)") (class "Default")
      (node (ref "Q16") (pin "1") (pinfunction "G_1") (pintype "passive"))
      (node (ref "R30") (pin "1") (pinfunction "1_1") (pintype "passive"))
      (node (ref "R31") (pin "2") (pinfunction "2_2") (pintype "passive"))
    )
    (net (code "40") (name "Net-(U1A-1IN+)") (class "Default")
      (node (ref "R26") (pin "2") (pinfunction "2_2") (pintype "passive"))
      (node (ref "U1") (pin "3") (pinfunction "1IN+_3") (pintype "input"))
    )
    (net (code "41") (name "Net-(U1B-2IN+)") (class "Default")
      (node (ref "R20") (pin "2") (pinfunction "2_2") (pintype "passive"))
      (node (ref "R21") (pin "1") (pinfunction "1_1") (pintype "passive"))
      (node (ref "U1") (pin "5") (pinfunction "2IN+_5") (pintype "input"))
    )
    (net (code "42") (name "Net-(U1B-2IN-)") (class "Default")
      (node (ref "R17") (pin "1") (pinfunction "1_1") (pintype "passive"))
      (node (ref "R19") (pin "2") (pinfunction "2_2") (pintype "passive"))
      (node (ref "U1") (pin "6") (pinfunction "2IN-_6") (pintype "input"))
    )
    (net (code "43") (name "Net-(U1C-3IN-)") (class "Default")
      (node (ref "R22") (pin "1") (pinfunction "1_1") (pintype "passive"))
      (node (ref "R25") (pin "2") (pinfunction "2_2") (pintype "passive"))
      (node (ref "U1") (pin "9") (pinfunction "3IN-_9") (pintype "input"))
    )
    (net (code "44") (name "Net-(U1C-3OUT)") (class "Default")
      (node (ref "R23") (pin "2") (pinfunction "2_2") (pintype "passive"))
      (node (ref "U1") (pin "8") (pinfunction "3OUT_8") (pintype "output"))
    )
    (net (code "45") (name "Net-(U1D-4IN+)") (class "Default")
      (node (ref "R18") (pin "2") (pinfunction "2_2") (pintype "passive"))
      (node (ref "U1") (pin "12") (pinfunction "4IN+_12") (pintype "input"))
    )
    (net (code "46") (name "VCC") (class "Default")
      (node (ref "LS1") (pin "LOAD+") (pinfunction "POS_LOAD+") (pintype "passive"))
      (node (ref "Q3") (pin "5-6-7-8") (pinfunction "D_5-6-7-8") (pintype "passive"))
      (node (ref "Q7") (pin "5-6-7-8") (pinfunction "D_5-6-7-8") (pintype "passive"))
      (node (ref "R11") (pin "1") (pinfunction "1_1") (pintype "passive"))
      (node (ref "R27") (pin "2") (pinfunction "2_2") (pintype "passive"))
    )
    (net (code "47") (name "unconnected-(U3-SHDN-Pad5)") (class "Default")
      (node (ref "U3") (pin "5") (pinfunction "SHDN_5") (pintype "input+no_connect"))
    )
  )
)
